# Laser7Segment.net
KiCad netlist of a schematic drawn in EAGLE
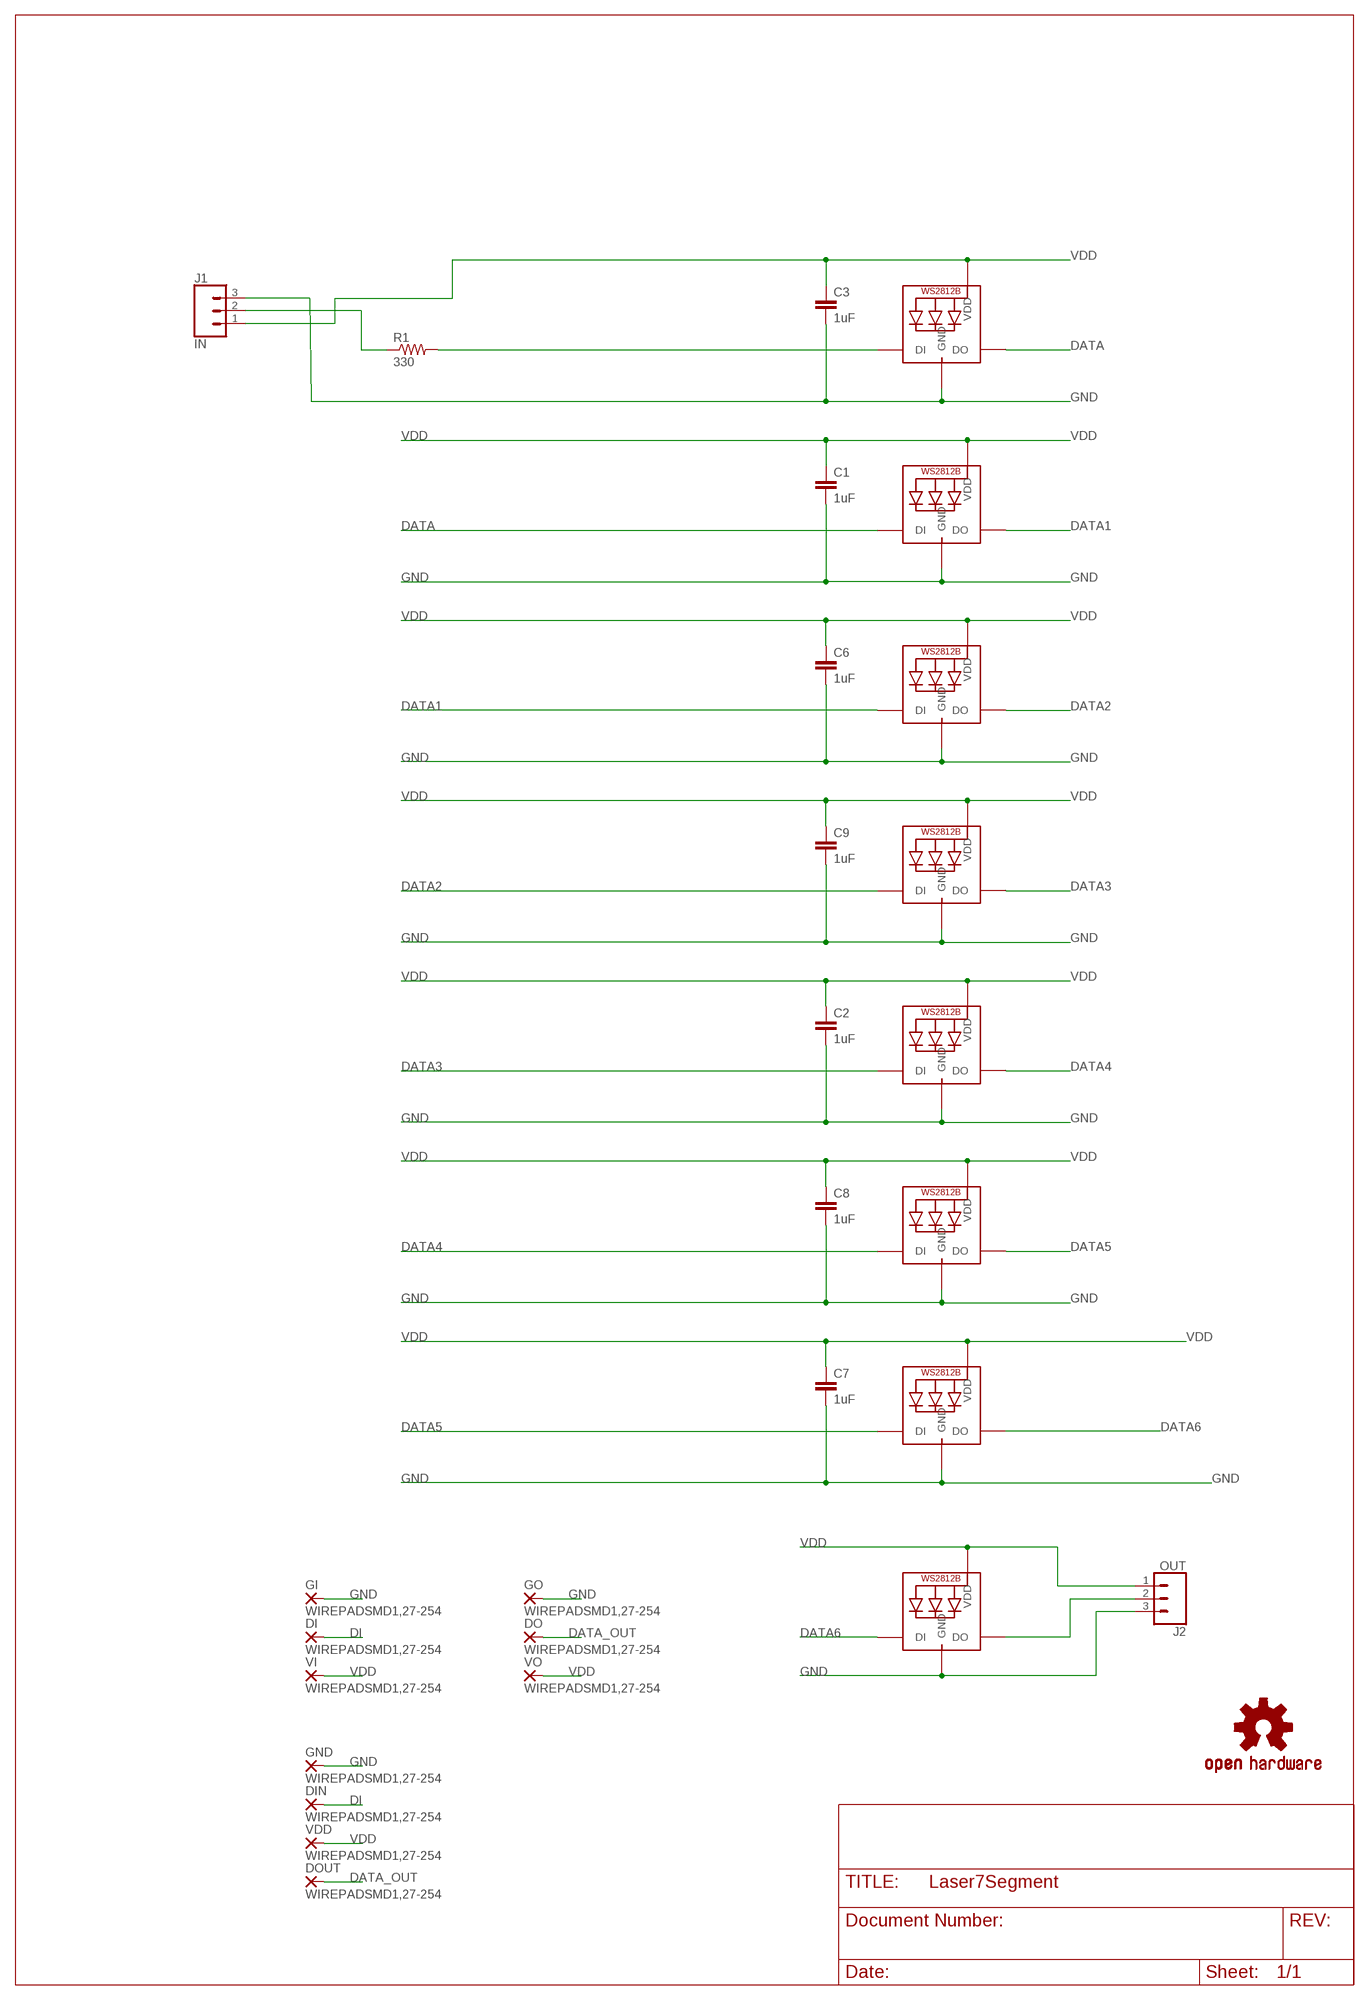
[diagram p0: schematic, sheet 1]

(export (version "E")
  (design (tool "Eeschema 10.0.6"))
  (components
    (comp (ref "C1")
      (value "1uF")
      (footprint "eagle-import:C0805")
      (libsource (lib "eagle-import") (part "C-EUC0805"))
    )
    (comp (ref "C2")
      (value "1uF")
      (footprint "eagle-import:C0805")
      (libsource (lib "eagle-import") (part "C-EUC0805"))
    )
    (comp (ref "C3")
      (value "1uF")
      (footprint "eagle-import:C0805")
      (libsource (lib "eagle-import") (part "C-EUC0805"))
    )
    (comp (ref "C6")
      (value "1uF")
      (footprint "eagle-import:C0805")
      (libsource (lib "eagle-import") (part "C-EUC0805"))
    )
    (comp (ref "C7")
      (value "1uF")
      (footprint "eagle-import:C0805")
      (libsource (lib "eagle-import") (part "C-EUC0805"))
    )
    (comp (ref "C8")
      (value "1uF")
      (footprint "eagle-import:C0805")
      (libsource (lib "eagle-import") (part "C-EUC0805"))
    )
    (comp (ref "C9")
      (value "1uF")
      (footprint "eagle-import:C0805")
      (libsource (lib "eagle-import") (part "C-EUC0805"))
    )
    (comp (ref "DI")
      (value "WIREPADSMD1,27-254")
      (footprint "eagle-import:SMD1,27-2,54")
      (libsource (lib "eagle-import") (part "WIREPADSMD1,27-254"))
    )
    (comp (ref "DIN")
      (value "WIREPADSMD1,27-254")
      (footprint "eagle-import:SMD1,27-2,54")
      (libsource (lib "eagle-import") (part "WIREPADSMD1,27-254"))
    )
    (comp (ref "DO")
      (value "WIREPADSMD1,27-254")
      (footprint "eagle-import:SMD1,27-2,54")
      (libsource (lib "eagle-import") (part "WIREPADSMD1,27-254"))
    )
    (comp (ref "DOUT")
      (value "WIREPADSMD1,27-254")
      (footprint "eagle-import:SMD1,27-2,54")
      (libsource (lib "eagle-import") (part "WIREPADSMD1,27-254"))
    )
    (comp (ref "GI")
      (value "WIREPADSMD1,27-254")
      (footprint "eagle-import:SMD1,27-2,54")
      (libsource (lib "eagle-import") (part "WIREPADSMD1,27-254"))
    )
    (comp (ref "GND")
      (value "WIREPADSMD1,27-254")
      (footprint "eagle-import:SMD1,27-2,54")
      (libsource (lib "eagle-import") (part "WIREPADSMD1,27-254"))
    )
    (comp (ref "GO")
      (value "WIREPADSMD1,27-254")
      (footprint "eagle-import:SMD1,27-2,54")
      (libsource (lib "eagle-import") (part "WIREPADSMD1,27-254"))
    )
    (comp (ref "J1")
      (value "IN")
      (footprint "eagle-import:1X03_LONGPADS")
      (libsource (lib "eagle-import") (part "CONN_03LONGPADS"))
    )
    (comp (ref "J2")
      (value "OUT")
      (footprint "eagle-import:1X03_LONGPADS")
      (libsource (lib "eagle-import") (part "CONN_03LONGPADS"))
    )
    (comp (ref "L1")
      (value "WS2812B5050")
      (footprint "eagle-import:WS2812B")
      (libsource (lib "eagle-import") (part "WS2812B5050"))
    )
    (comp (ref "L2")
      (value "WS2812B5050")
      (footprint "eagle-import:WS2812B")
      (libsource (lib "eagle-import") (part "WS2812B5050"))
    )
    (comp (ref "L3")
      (value "WS2812B5050")
      (footprint "eagle-import:WS2812B")
      (libsource (lib "eagle-import") (part "WS2812B5050"))
    )
    (comp (ref "L4")
      (value "WS2812B5050")
      (footprint "eagle-import:WS2812B")
      (libsource (lib "eagle-import") (part "WS2812B5050"))
    )
    (comp (ref "L5")
      (value "WS2812B5050")
      (footprint "eagle-import:WS2812B")
      (libsource (lib "eagle-import") (part "WS2812B5050"))
    )
    (comp (ref "L6")
      (value "WS2812B5050")
      (footprint "eagle-import:WS2812B")
      (libsource (lib "eagle-import") (part "WS2812B5050"))
    )
    (comp (ref "L7")
      (value "WS2812B5050")
      (footprint "eagle-import:WS2812B")
      (libsource (lib "eagle-import") (part "WS2812B5050"))
    )
    (comp (ref "L8")
      (value "RGB 3535")
      (footprint "eagle-import:LED3535")
      (libsource (lib "eagle-import") (part "WS2812B3535"))
    )
    (comp (ref "LOGO1")
      (value "OSHW-LOGOM")
      (footprint "eagle-import:OSHW-LOGO-M")
      (libsource (lib "eagle-import") (part "OSHW-LOGOM"))
    )
    (comp (ref "R1")
      (value "330")
      (footprint "eagle-import:R0805")
      (libsource (lib "eagle-import") (part "R-US_R0805"))
    )
    (comp (ref "VDD")
      (value "WIREPADSMD1,27-254")
      (footprint "eagle-import:SMD1,27-2,54")
      (libsource (lib "eagle-import") (part "WIREPADSMD1,27-254"))
    )
    (comp (ref "VI")
      (value "WIREPADSMD1,27-254")
      (footprint "eagle-import:SMD1,27-2,54")
      (libsource (lib "eagle-import") (part "WIREPADSMD1,27-254"))
    )
    (comp (ref "VO")
      (value "WIREPADSMD1,27-254")
      (footprint "eagle-import:SMD1,27-2,54")
      (libsource (lib "eagle-import") (part "WIREPADSMD1,27-254"))
    )
  )
  (nets
    (net (code "1") (name "/DATA") (class "Default")
      (node (ref "L1") (pin "2-DOUT") (pinfunction "DO_2-DOUT") (pintype "output"))
      (node (ref "L2") (pin "4-DIN") (pinfunction "DI_4-DIN") (pintype "input"))
    )
    (net (code "2") (name "/DATA1") (class "Default")
      (node (ref "L2") (pin "2-DOUT") (pinfunction "DO_2-DOUT") (pintype "output"))
      (node (ref "L3") (pin "4-DIN") (pinfunction "DI_4-DIN") (pintype "input"))
    )
    (net (code "3") (name "/DATA2") (class "Default")
      (node (ref "L3") (pin "2-DOUT") (pinfunction "DO_2-DOUT") (pintype "output"))
      (node (ref "L4") (pin "4-DIN") (pinfunction "DI_4-DIN") (pintype "input"))
    )
    (net (code "4") (name "/DATA3") (class "Default")
      (node (ref "L4") (pin "2-DOUT") (pinfunction "DO_2-DOUT") (pintype "output"))
      (node (ref "L5") (pin "4-DIN") (pinfunction "DI_4-DIN") (pintype "input"))
    )
    (net (code "5") (name "/DATA4") (class "Default")
      (node (ref "L5") (pin "2-DOUT") (pinfunction "DO_2-DOUT") (pintype "output"))
      (node (ref "L6") (pin "4-DIN") (pinfunction "DI_4-DIN") (pintype "input"))
    )
    (net (code "6") (name "/DATA5") (class "Default")
      (node (ref "L6") (pin "2-DOUT") (pinfunction "DO_2-DOUT") (pintype "output"))
      (node (ref "L7") (pin "4-DIN") (pinfunction "DI_4-DIN") (pintype "input"))
    )
    (net (code "7") (name "/DATA6") (class "Default")
      (node (ref "L7") (pin "2-DOUT") (pinfunction "DO_2-DOUT") (pintype "output"))
      (node (ref "L8") (pin "1") (pinfunction "DI_1") (pintype "input"))
    )
    (net (code "8") (name "/DATA_OUT") (class "Default")
      (node (ref "DO") (pin "1") (pinfunction "P_1") (pintype "passive"))
      (node (ref "DOUT") (pin "1") (pinfunction "P_1") (pintype "passive"))
      (node (ref "J2") (pin "2") (pinfunction "2_2") (pintype "passive"))
      (node (ref "L8") (pin "3") (pinfunction "DO_3") (pintype "output"))
    )
    (net (code "9") (name "/DI") (class "Default")
      (node (ref "DI") (pin "1") (pinfunction "P_1") (pintype "passive"))
      (node (ref "DIN") (pin "1") (pinfunction "P_1") (pintype "passive"))
      (node (ref "J1") (pin "2") (pinfunction "2_2") (pintype "passive"))
      (node (ref "R1") (pin "1") (pinfunction "1_1") (pintype "passive"))
    )
    (net (code "10") (name "/GND") (class "Default")
      (node (ref "C1") (pin "2") (pinfunction "2_2") (pintype "passive"))
      (node (ref "C2") (pin "2") (pinfunction "2_2") (pintype "passive"))
      (node (ref "C3") (pin "2") (pinfunction "2_2") (pintype "passive"))
      (node (ref "C6") (pin "2") (pinfunction "2_2") (pintype "passive"))
      (node (ref "C7") (pin "2") (pinfunction "2_2") (pintype "passive"))
      (node (ref "C8") (pin "2") (pinfunction "2_2") (pintype "passive"))
      (node (ref "C9") (pin "2") (pinfunction "2_2") (pintype "passive"))
      (node (ref "GI") (pin "1") (pinfunction "P_1") (pintype "passive"))
      (node (ref "GND") (pin "1") (pinfunction "P_1") (pintype "passive"))
      (node (ref "GO") (pin "1") (pinfunction "P_1") (pintype "passive"))
      (node (ref "J1") (pin "3") (pinfunction "3_3") (pintype "passive"))
      (node (ref "J2") (pin "3") (pinfunction "3_3") (pintype "passive"))
      (node (ref "L1") (pin "3-GND") (pinfunction "GND_3-GND") (pintype "power_in"))
      (node (ref "L2") (pin "3-GND") (pinfunction "GND_3-GND") (pintype "power_in"))
      (node (ref "L3") (pin "3-GND") (pinfunction "GND_3-GND") (pintype "power_in"))
      (node (ref "L4") (pin "3-GND") (pinfunction "GND_3-GND") (pintype "power_in"))
      (node (ref "L5") (pin "3-GND") (pinfunction "GND_3-GND") (pintype "power_in"))
      (node (ref "L6") (pin "3-GND") (pinfunction "GND_3-GND") (pintype "power_in"))
      (node (ref "L7") (pin "3-GND") (pinfunction "GND_3-GND") (pintype "power_in"))
      (node (ref "L8") (pin "4") (pinfunction "GND_4") (pintype "power_in"))
    )
    (net (code "11") (name "/VDD") (class "Default")
      (node (ref "C1") (pin "1") (pinfunction "1_1") (pintype "passive"))
      (node (ref "C2") (pin "1") (pinfunction "1_1") (pintype "passive"))
      (node (ref "C3") (pin "1") (pinfunction "1_1") (pintype "passive"))
      (node (ref "C6") (pin "1") (pinfunction "1_1") (pintype "passive"))
      (node (ref "C7") (pin "1") (pinfunction "1_1") (pintype "passive"))
      (node (ref "C8") (pin "1") (pinfunction "1_1") (pintype "passive"))
      (node (ref "C9") (pin "1") (pinfunction "1_1") (pintype "passive"))
      (node (ref "J1") (pin "1") (pinfunction "1_1") (pintype "passive"))
      (node (ref "J2") (pin "1") (pinfunction "1_1") (pintype "passive"))
      (node (ref "L1") (pin "1-VDD") (pinfunction "VDD_1-VDD") (pintype "power_in"))
      (node (ref "L2") (pin "1-VDD") (pinfunction "VDD_1-VDD") (pintype "power_in"))
      (node (ref "L3") (pin "1-VDD") (pinfunction "VDD_1-VDD") (pintype "power_in"))
      (node (ref "L4") (pin "1-VDD") (pinfunction "VDD_1-VDD") (pintype "power_in"))
      (node (ref "L5") (pin "1-VDD") (pinfunction "VDD_1-VDD") (pintype "power_in"))
      (node (ref "L6") (pin "1-VDD") (pinfunction "VDD_1-VDD") (pintype "power_in"))
      (node (ref "L7") (pin "1-VDD") (pinfunction "VDD_1-VDD") (pintype "power_in"))
      (node (ref "L8") (pin "2") (pinfunction "VDD_2") (pintype "power_in"))
      (node (ref "VDD") (pin "1") (pinfunction "P_1") (pintype "passive"))
      (node (ref "VI") (pin "1") (pinfunction "P_1") (pintype "passive"))
      (node (ref "VO") (pin "1") (pinfunction "P_1") (pintype "passive"))
    )
    (net (code "12") (name "Net-(L1-DI)") (class "Default")
      (node (ref "L1") (pin "4-DIN") (pinfunction "DI_4-DIN") (pintype "input"))
      (node (ref "R1") (pin "2") (pinfunction "2_2") (pintype "passive"))
    )
  )
)
